# main_processor.net
KiCad netlist of a schematic drawn in Altium Designer
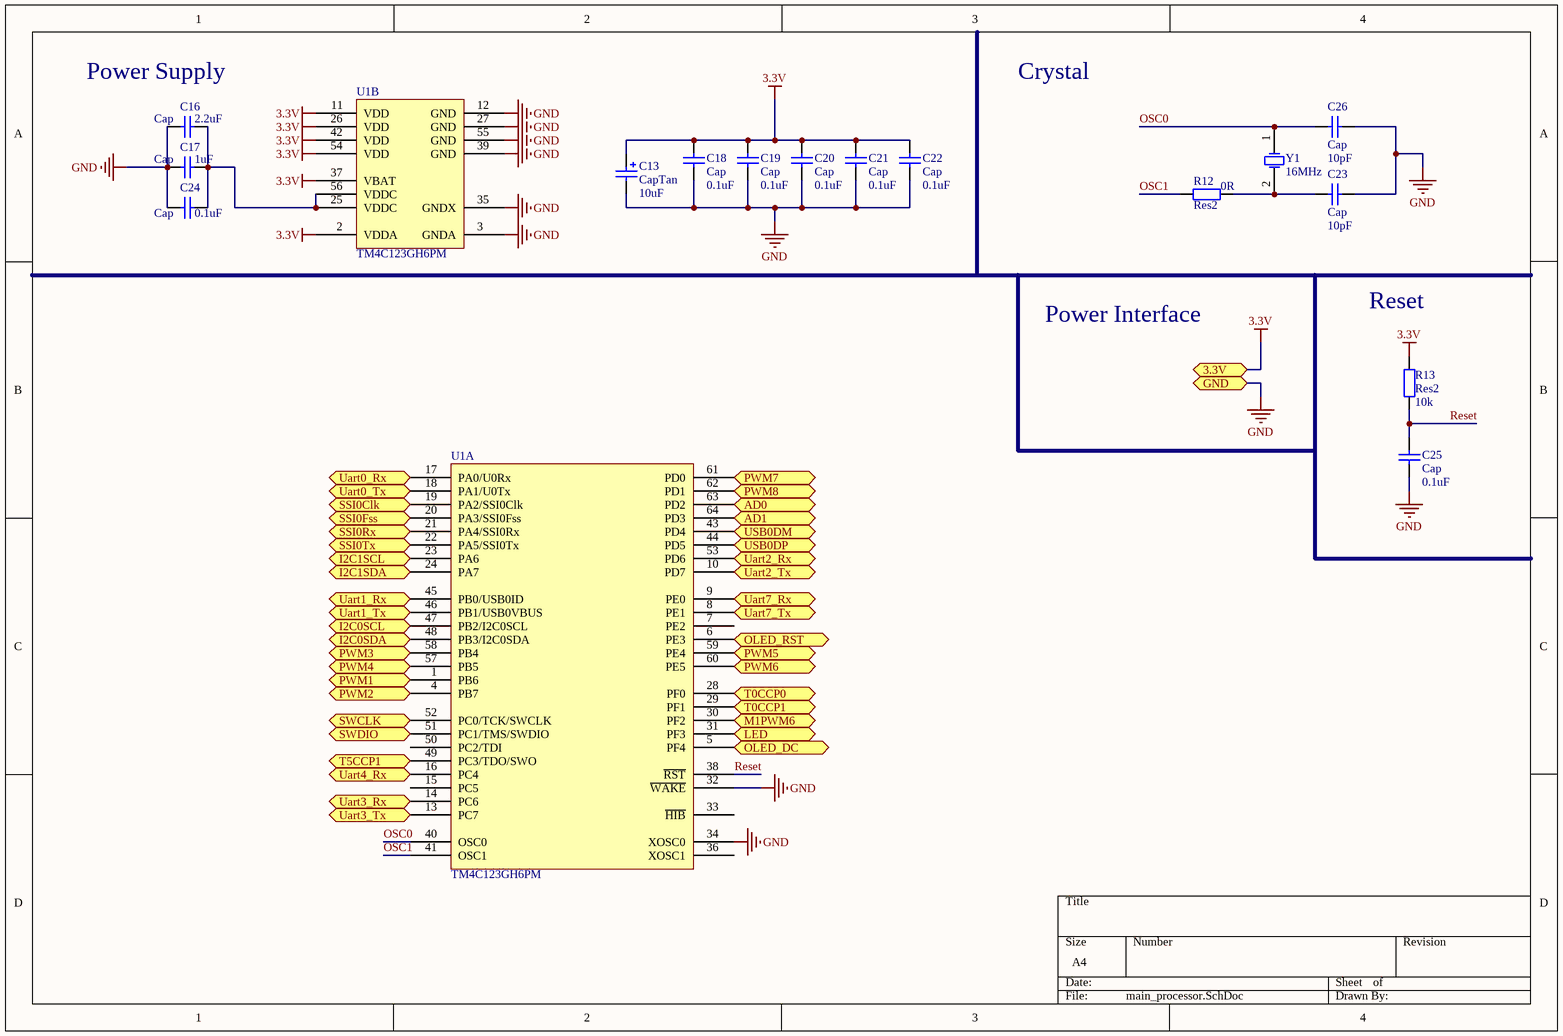
[diagram p0: main_processor.SchDoc]

(export (version "E")
  (design (tool "Eeschema 10.0.6"))
  (components
    (comp (ref "C13")
      (value "CapTan")
      (footprint "1206_P")
      (description "Polarized Capacitor (Axial)")
      (fields (field (name "ALTIUM_VALUE") "10uF") (field (name "PUBLISHER") "Altium Limited"))
      (libsource (lib "Miscellaneous Devices") (part "Cap Pol2"))
    )
    (comp (ref "C16")
      (value "Cap")
      (footprint "0603")
      (description "Capacitor")
      (fields (field (name "ALTIUM_VALUE") "2.2uF") (field (name "PUBLISHER") "Altium Limited"))
      (libsource (lib "Miscellaneous Devices") (part "Cap"))
    )
    (comp (ref "C17")
      (value "Cap")
      (footprint "0603")
      (description "Capacitor")
      (fields (field (name "ALTIUM_VALUE") "1uF") (field (name "PUBLISHER") "Altium Limited"))
      (libsource (lib "Miscellaneous Devices") (part "Cap"))
    )
    (comp (ref "C18")
      (value "Cap")
      (footprint "0603")
      (description "Capacitor")
      (fields (field (name "ALTIUM_VALUE") "0.1uF") (field (name "PUBLISHER") "Altium Limited"))
      (libsource (lib "Miscellaneous Devices") (part "Cap"))
    )
    (comp (ref "C19")
      (value "Cap")
      (footprint "0603")
      (description "Capacitor")
      (fields (field (name "ALTIUM_VALUE") "0.1uF") (field (name "PUBLISHER") "Altium Limited"))
      (libsource (lib "Miscellaneous Devices") (part "Cap"))
    )
    (comp (ref "C20")
      (value "Cap")
      (footprint "0603")
      (description "Capacitor")
      (fields (field (name "ALTIUM_VALUE") "0.1uF") (field (name "PUBLISHER") "Altium Limited"))
      (libsource (lib "Miscellaneous Devices") (part "Cap"))
    )
    (comp (ref "C21")
      (value "Cap")
      (footprint "0603")
      (description "Capacitor")
      (fields (field (name "ALTIUM_VALUE") "0.1uF") (field (name "PUBLISHER") "Altium Limited"))
      (libsource (lib "Miscellaneous Devices") (part "Cap"))
    )
    (comp (ref "C22")
      (value "Cap")
      (footprint "0603")
      (description "Capacitor")
      (fields (field (name "ALTIUM_VALUE") "0.1uF") (field (name "PUBLISHER") "Altium Limited"))
      (libsource (lib "Miscellaneous Devices") (part "Cap"))
    )
    (comp (ref "C23")
      (value "Cap")
      (footprint "0603")
      (description "Capacitor")
      (fields (field (name "ALTIUM_VALUE") "10pF") (field (name "PUBLISHER") "Altium Limited"))
      (libsource (lib "Miscellaneous Devices") (part "Cap"))
    )
    (comp (ref "C24")
      (value "Cap")
      (footprint "0603")
      (description "Capacitor")
      (fields (field (name "ALTIUM_VALUE") "0.1uF") (field (name "PUBLISHER") "Altium Limited"))
      (libsource (lib "Miscellaneous Devices") (part "Cap"))
    )
    (comp (ref "C25")
      (value "Cap")
      (footprint "0603")
      (description "Capacitor")
      (fields (field (name "ALTIUM_VALUE") "0.1uF") (field (name "PUBLISHER") "Altium Limited"))
      (libsource (lib "Miscellaneous Devices") (part "Cap"))
    )
    (comp (ref "C26")
      (value "Cap")
      (footprint "0603")
      (description "Capacitor")
      (fields (field (name "ALTIUM_VALUE") "10pF") (field (name "PUBLISHER") "Altium Limited"))
      (libsource (lib "Miscellaneous Devices") (part "Cap"))
    )
    (comp (ref "R12")
      (value "Res2")
      (footprint "0603")
      (description "Resistor")
      (fields (field (name "ALTIUM_VALUE") "0R") (field (name "PUBLISHER") "Altium Limited"))
      (libsource (lib "Miscellaneous Devices") (part "Res2"))
    )
    (comp (ref "R13")
      (value "Res2")
      (footprint "0603")
      (description "Resistor")
      (fields (field (name "ALTIUM_VALUE") "10k") (field (name "PUBLISHER") "Altium Limited"))
      (libsource (lib "") (part "Res2_1"))
    )
    (comp (ref "U1")
      (value "TM4C123GH6PM")
      (footprint "TI-PQFP-G64")
      (libsource (lib "SchlibProcessor") (part "TM4C123GH6PM"))
    )
    (comp (ref "Y1")
      (value "16MHz")
      (footprint "Crystal_SMD_3225")
      (description "Crystal Oscillator")
      (fields (field (name "PUBLISHER") "Altium Limited"))
      (libsource (lib "Explorer STM32F407封装库") (part "XTAL"))
    )
  )
  (nets
    (net (code "1") (name "/AD0") (class "Default")
      (node (ref "U1") (pin "63") (pinfunction "PD2_63") (pintype "passive"))
    )
    (net (code "2") (name "/AD1") (class "Default")
      (node (ref "U1") (pin "64") (pinfunction "PD3_64") (pintype "passive"))
    )
    (net (code "3") (name "/I2C0SCL") (class "Default")
      (node (ref "U1") (pin "47") (pinfunction "PB2/I2C0SCL_47") (pintype "passive"))
    )
    (net (code "4") (name "/I2C0SDA") (class "Default")
      (node (ref "U1") (pin "48") (pinfunction "PB3/I2C0SDA_48") (pintype "passive"))
    )
    (net (code "5") (name "/I2C1SCL") (class "Default")
      (node (ref "U1") (pin "23") (pinfunction "PA6_23") (pintype "passive"))
    )
    (net (code "6") (name "/I2C1SDA") (class "Default")
      (node (ref "U1") (pin "24") (pinfunction "PA7_24") (pintype "passive"))
    )
    (net (code "7") (name "/LED") (class "Default")
      (node (ref "U1") (pin "31") (pinfunction "PF3_31") (pintype "passive"))
    )
    (net (code "8") (name "/M1PWM6") (class "Default")
      (node (ref "U1") (pin "30") (pinfunction "PF2_30") (pintype "passive"))
    )
    (net (code "9") (name "/OLED_DC") (class "Default")
      (node (ref "U1") (pin "5") (pinfunction "PF4_5") (pintype "passive"))
    )
    (net (code "10") (name "/OLED_RST") (class "Default")
      (node (ref "U1") (pin "6") (pinfunction "PE3_6") (pintype "passive"))
    )
    (net (code "11") (name "/OSC0") (class "Default")
      (node (ref "C26") (pin "2") (pinfunction "2_2") (pintype "passive"))
      (node (ref "U1") (pin "40") (pinfunction "OSC0_40") (pintype "passive"))
      (node (ref "Y1") (pin "1") (pinfunction "OSC1_1") (pintype "passive"))
    )
    (net (code "12") (name "/OSC1") (class "Default")
      (node (ref "R12") (pin "1") (pinfunction "1_1") (pintype "passive"))
      (node (ref "U1") (pin "41") (pinfunction "OSC1_41") (pintype "passive"))
    )
    (net (code "13") (name "/PWM1") (class "Default")
      (node (ref "U1") (pin "1") (pinfunction "PB6_1") (pintype "passive"))
    )
    (net (code "14") (name "/PWM2") (class "Default")
      (node (ref "U1") (pin "4") (pinfunction "PB7_4") (pintype "passive"))
    )
    (net (code "15") (name "/PWM3") (class "Default")
      (node (ref "U1") (pin "58") (pinfunction "PB4_58") (pintype "passive"))
    )
    (net (code "16") (name "/PWM4") (class "Default")
      (node (ref "U1") (pin "57") (pinfunction "PB5_57") (pintype "passive"))
    )
    (net (code "17") (name "/PWM5") (class "Default")
      (node (ref "U1") (pin "59") (pinfunction "PE4_59") (pintype "passive"))
    )
    (net (code "18") (name "/PWM6") (class "Default")
      (node (ref "U1") (pin "60") (pinfunction "PE5_60") (pintype "passive"))
    )
    (net (code "19") (name "/PWM7") (class "Default")
      (node (ref "U1") (pin "61") (pinfunction "PD0_61") (pintype "passive"))
    )
    (net (code "20") (name "/PWM8") (class "Default")
      (node (ref "U1") (pin "62") (pinfunction "PD1_62") (pintype "passive"))
    )
    (net (code "21") (name "/Reset") (class "Default")
      (node (ref "C25") (pin "2") (pinfunction "2_2") (pintype "passive"))
      (node (ref "R13") (pin "1") (pinfunction "1_1") (pintype "passive"))
      (node (ref "U1") (pin "38") (pinfunction "~{RST}_38") (pintype "passive"))
    )
    (net (code "22") (name "/SSI0Clk") (class "Default")
      (node (ref "U1") (pin "19") (pinfunction "PA2/SSI0Clk_19") (pintype "passive"))
    )
    (net (code "23") (name "/SSI0Fss") (class "Default")
      (node (ref "U1") (pin "20") (pinfunction "PA3/SSI0Fss_20") (pintype "passive"))
    )
    (net (code "24") (name "/SSI0Rx") (class "Default")
      (node (ref "U1") (pin "21") (pinfunction "PA4/SSI0Rx_21") (pintype "passive"))
    )
    (net (code "25") (name "/SSI0Tx") (class "Default")
      (node (ref "U1") (pin "22") (pinfunction "PA5/SSI0Tx_22") (pintype "passive"))
    )
    (net (code "26") (name "/SWCLK") (class "Default")
      (node (ref "U1") (pin "52") (pinfunction "PC0/TCK/SWCLK_52") (pintype "passive"))
    )
    (net (code "27") (name "/SWDIO") (class "Default")
      (node (ref "U1") (pin "51") (pinfunction "PC1/TMS/SWDIO_51") (pintype "passive"))
    )
    (net (code "28") (name "/T0CCP0") (class "Default")
      (node (ref "U1") (pin "28") (pinfunction "PF0_28") (pintype "passive"))
    )
    (net (code "29") (name "/T0CCP1") (class "Default")
      (node (ref "U1") (pin "29") (pinfunction "PF1_29") (pintype "passive"))
    )
    (net (code "30") (name "/T5CCP1") (class "Default")
      (node (ref "U1") (pin "49") (pinfunction "PC3/TDO/SWO_49") (pintype "passive"))
    )
    (net (code "31") (name "/USB0DM") (class "Default")
      (node (ref "U1") (pin "43") (pinfunction "PD4_43") (pintype "passive"))
    )
    (net (code "32") (name "/USB0DP") (class "Default")
      (node (ref "U1") (pin "44") (pinfunction "PD5_44") (pintype "passive"))
    )
    (net (code "33") (name "/Uart0_Rx") (class "Default")
      (node (ref "U1") (pin "17") (pinfunction "PA0/U0Rx_17") (pintype "passive"))
    )
    (net (code "34") (name "/Uart0_Tx") (class "Default")
      (node (ref "U1") (pin "18") (pinfunction "PA1/U0Tx_18") (pintype "passive"))
    )
    (net (code "35") (name "/Uart1_Rx") (class "Default")
      (node (ref "U1") (pin "45") (pinfunction "PB0/USB0ID_45") (pintype "passive"))
    )
    (net (code "36") (name "/Uart1_Tx") (class "Default")
      (node (ref "U1") (pin "46") (pinfunction "PB1/USB0VBUS_46") (pintype "passive"))
    )
    (net (code "37") (name "/Uart2_Rx") (class "Default")
      (node (ref "U1") (pin "53") (pinfunction "PD6_53") (pintype "passive"))
    )
    (net (code "38") (name "/Uart2_Tx") (class "Default")
      (node (ref "U1") (pin "10") (pinfunction "PD7_10") (pintype "passive"))
    )
    (net (code "39") (name "/Uart3_Rx") (class "Default")
      (node (ref "U1") (pin "14") (pinfunction "PC6_14") (pintype "passive"))
    )
    (net (code "40") (name "/Uart3_Tx") (class "Default")
      (node (ref "U1") (pin "13") (pinfunction "PC7_13") (pintype "passive"))
    )
    (net (code "41") (name "/Uart4_Rx") (class "Default")
      (node (ref "U1") (pin "16") (pinfunction "PC4_16") (pintype "passive"))
    )
    (net (code "42") (name "/Uart7_Rx") (class "Default")
      (node (ref "U1") (pin "9") (pinfunction "PE0_9") (pintype "passive"))
    )
    (net (code "43") (name "/Uart7_Tx") (class "Default")
      (node (ref "U1") (pin "8") (pinfunction "PE1_8") (pintype "passive"))
    )
    (net (code "44") (name "3.3V") (class "Default")
      (node (ref "C13") (pin "1") (pinfunction "1_1") (pintype "passive"))
      (node (ref "C18") (pin "2") (pinfunction "2_2") (pintype "passive"))
      (node (ref "C19") (pin "2") (pinfunction "2_2") (pintype "passive"))
      (node (ref "C20") (pin "2") (pinfunction "2_2") (pintype "passive"))
      (node (ref "C21") (pin "2") (pinfunction "2_2") (pintype "passive"))
      (node (ref "C22") (pin "2") (pinfunction "2_2") (pintype "passive"))
      (node (ref "R13") (pin "2") (pinfunction "2_2") (pintype "passive"))
      (node (ref "U1") (pin "11") (pinfunction "VDD_11") (pintype "power_in"))
      (node (ref "U1") (pin "2") (pinfunction "VDDA_2") (pintype "power_in"))
      (node (ref "U1") (pin "26") (pinfunction "VDD_26") (pintype "power_in"))
      (node (ref "U1") (pin "37") (pinfunction "VBAT_37") (pintype "power_in"))
      (node (ref "U1") (pin "42") (pinfunction "VDD_42") (pintype "power_in"))
      (node (ref "U1") (pin "54") (pinfunction "VDD_54") (pintype "power_in"))
    )
    (net (code "45") (name "GND") (class "Default")
      (node (ref "C13") (pin "2") (pinfunction "2_2") (pintype "passive"))
      (node (ref "C16") (pin "1") (pinfunction "1_1") (pintype "passive"))
      (node (ref "C17") (pin "1") (pinfunction "1_1") (pintype "passive"))
      (node (ref "C18") (pin "1") (pinfunction "1_1") (pintype "passive"))
      (node (ref "C19") (pin "1") (pinfunction "1_1") (pintype "passive"))
      (node (ref "C20") (pin "1") (pinfunction "1_1") (pintype "passive"))
      (node (ref "C21") (pin "1") (pinfunction "1_1") (pintype "passive"))
      (node (ref "C22") (pin "1") (pinfunction "1_1") (pintype "passive"))
      (node (ref "C23") (pin "1") (pinfunction "1_1") (pintype "passive"))
      (node (ref "C24") (pin "1") (pinfunction "1_1") (pintype "passive"))
      (node (ref "C25") (pin "1") (pinfunction "1_1") (pintype "passive"))
      (node (ref "C26") (pin "1") (pinfunction "1_1") (pintype "passive"))
      (node (ref "U1") (pin "12") (pinfunction "GND_12") (pintype "power_in"))
      (node (ref "U1") (pin "27") (pinfunction "GND_27") (pintype "power_in"))
      (node (ref "U1") (pin "3") (pinfunction "GNDA_3") (pintype "power_in"))
      (node (ref "U1") (pin "32") (pinfunction "~{WAKE}_32") (pintype "passive"))
      (node (ref "U1") (pin "34") (pinfunction "XOSC0_34") (pintype "passive"))
      (node (ref "U1") (pin "35") (pinfunction "GNDX_35") (pintype "power_in"))
      (node (ref "U1") (pin "39") (pinfunction "GND_39") (pintype "power_in"))
      (node (ref "U1") (pin "55") (pinfunction "GND_55") (pintype "power_in"))
    )
    (net (code "46") (name "Net-(C16-Pad2)") (class "Default")
      (node (ref "C16") (pin "2") (pinfunction "2_2") (pintype "passive"))
      (node (ref "C17") (pin "2") (pinfunction "2_2") (pintype "passive"))
      (node (ref "C24") (pin "2") (pinfunction "2_2") (pintype "passive"))
      (node (ref "U1") (pin "25") (pinfunction "VDDC_25") (pintype "power_in"))
      (node (ref "U1") (pin "56") (pinfunction "VDDC_56") (pintype "power_in"))
    )
    (net (code "47") (name "Net-(Y1-OSC2)") (class "Default")
      (node (ref "C23") (pin "2") (pinfunction "2_2") (pintype "passive"))
      (node (ref "R12") (pin "2") (pinfunction "2_2") (pintype "passive"))
      (node (ref "Y1") (pin "2") (pinfunction "OSC2_2") (pintype "passive"))
    )
    (net (code "48") (name "unconnected-(U1A-PC2{slash}TDI-Pad50)") (class "Default")
      (node (ref "U1") (pin "50") (pinfunction "PC2/TDI_50") (pintype "passive"))
    )
    (net (code "49") (name "unconnected-(U1A-PC5-Pad15)") (class "Default")
      (node (ref "U1") (pin "15") (pinfunction "PC5_15") (pintype "passive"))
    )
    (net (code "50") (name "unconnected-(U1A-PE2-Pad7)") (class "Default")
      (node (ref "U1") (pin "7") (pinfunction "PE2_7") (pintype "passive"))
    )
    (net (code "51") (name "unconnected-(U1A-XOSC1-Pad36)") (class "Default")
      (node (ref "U1") (pin "36") (pinfunction "XOSC1_36") (pintype "passive"))
    )
    (net (code "52") (name "unconnected-(U1A-~{HIB}-Pad33)") (class "Default")
      (node (ref "U1") (pin "33") (pinfunction "~{HIB}_33") (pintype "passive"))
    )
  )
)
